# deel1_voeding.net
KiCad netlist of a schematic drawn in Altium Designer
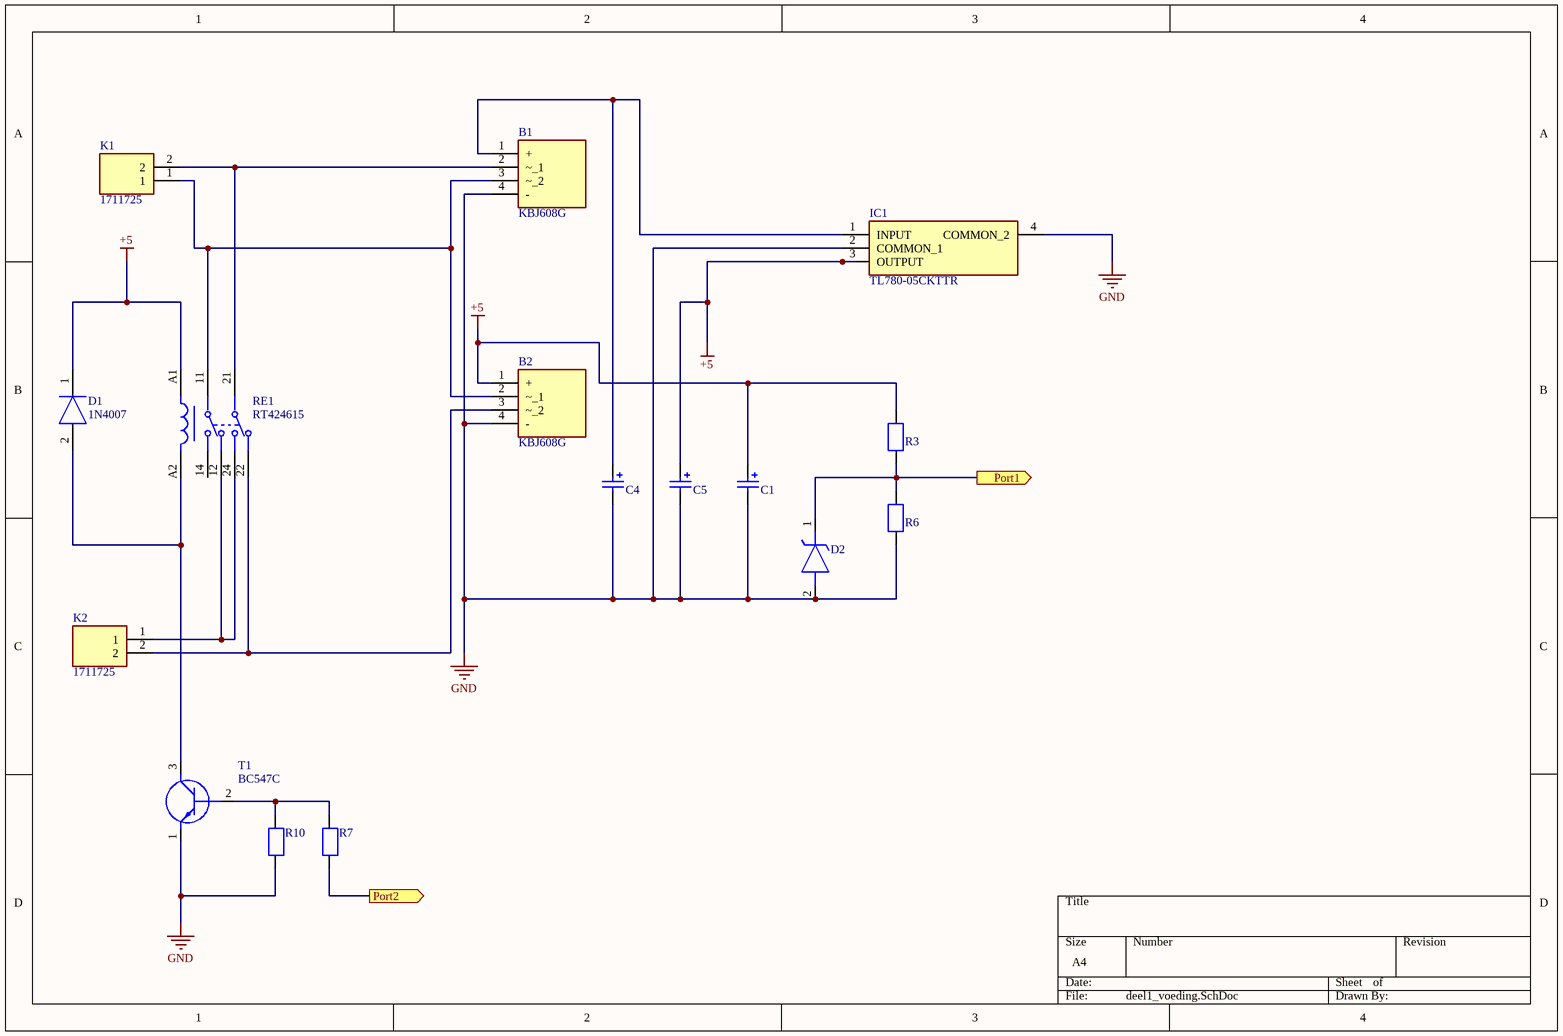
[diagram p0: deel1_voeding.SchDoc]

(export (version "E")
  (design (tool "Eeschema 10.0.6"))
  (components
    (comp (ref "B1")
      (value "KBJ608G")
      (footprint "SamacSys:TO750P480X2500X1900-4P")
      (description "Bridge Rectifier")
      (fields (field (name "MOUSER PART NUMBER") "621-KBJ608G"))
      (libsource (lib "SoldeerboutLib") (part "KBJ608G"))
    )
    (comp (ref "B2")
      (value "KBJ608G")
      (footprint "SamacSys:TO750P480X2500X1900-4P")
      (description "Bridge Rectifier")
      (fields (field (name "MOUSER PART NUMBER") "621-KBJ608G"))
      (libsource (lib "SoldeerboutLib") (part "KBJ608G"))
    )
    (comp (ref "C1")
      (value "4700uF")
      (footprint "WCAP-ATG8_D22H41")
      (description "WCAP-ATG8 Aluminum Electrolytic Capacitor, Radial THT, D22xH41mm, 4700uF, 50V")
      (fields
        (field (name "MANUFACTURER") "Wurth Elektronik")
        (field (name "MANUFACTURER PART NUMBER") "860010683032")
      )
      (libsource (lib "SoldeerboutLib") (part "860010683032"))
    )
    (comp (ref "C4")
      (value "100uF")
      (footprint "WCAP-ATG8_D8H11.5")
      (description "WCAP-ATG8 Aluminum Electrolytic Capacitor, Radial THT, D8xH11.5mm, 100uF, 50V")
      (fields
        (field (name "MANUFACTURER") "Wurth Elektronik")
        (field (name "MANUFACTURER PART NUMBER") "860010674014")
      )
      (libsource (lib "SoldeerboutLib") (part "860010674014"))
    )
    (comp (ref "C5")
      (value "10uF")
      (footprint "WCAP-ATG8_D5H11")
      (description "WCAP-ATG8 Aluminum Electrolytic Capacitor, Radial THT, D5xH11mm, 10uF, 50V")
      (fields
        (field (name "MANUFACTURER") "Wurth Elektronik")
        (field (name "MANUFACTURER PART NUMBER") "860010672009")
      )
      (libsource (lib "SoldeerboutLib") (part "860010672009"))
    )
    (comp (ref "D1")
      (value "1N4007")
      (footprint "SamacSys:DIOM5327X242N")
      (description "Diode")
      (libsource (lib "SoldeerboutLib") (part "1N4007"))
    )
    (comp (ref "D2")
      (value "1N4106")
      (footprint "SamacSys:DIOAD1256W51L444D203")
      (description "Zener Diode")
      (fields (field (name "MOUSER PART NUMBER") "494-1N4106"))
      (libsource (lib "SoldeerboutLib") (part "1N4106"))
    )
    (comp (ref "IC1")
      (value "TL780-05CKTTR")
      (footprint "SamacSys:TL78005CKTTR")
      (description "Integrated Circuit")
      (fields (field (name "MOUSER PART NUMBER") "595-TL780-05CKTTR"))
      (libsource (lib "SoldeerboutLib") (part "TL780-05CKTTR"))
    )
    (comp (ref "K1")
      (value "1711725")
      (footprint "SamacSys:1711725")
      (description "Connector")
      (fields (field (name "MOUSER PART NUMBER") "651-1711725"))
      (libsource (lib "SoldeerboutLib") (part "1711725"))
    )
    (comp (ref "K2")
      (value "1711725")
      (footprint "SamacSys:1711725")
      (description "Connector")
      (fields (field (name "MOUSER PART NUMBER") "651-1711725"))
      (libsource (lib "") (part "1711725_1"))
    )
    (comp (ref "R3")
      (value "CRCW08050000Z0EA")
      (footprint "RESC2013X50X30LL20T20")
      (fields (field (name "MANUFACTURER") "Vishay Dale"))
      (libsource (lib "SoldeerboutLib") (part "resistor"))
    )
    (comp (ref "R6")
      (value "CRCW08050000Z0EA")
      (footprint "RESC2013X50X30LL20T20")
      (fields (field (name "MANUFACTURER") "Vishay Dale"))
      (libsource (lib "SoldeerboutLib") (part "resistor"))
    )
    (comp (ref "R7")
      (value "CRCW08050000Z0EA")
      (footprint "RESC2013X50X30LL20T20")
      (description "10k")
      (fields (field (name "MANUFACTURER") "Vishay Dale"))
      (libsource (lib "SoldeerboutLib") (part "resistor"))
    )
    (comp (ref "R10")
      (value "CRCW08050000Z0EA")
      (footprint "RESC2013X50X30LL20T20")
      (description "4k7")
      (fields (field (name "MANUFACTURER") "Vishay Dale"))
      (libsource (lib "SoldeerboutLib") (part "resistor"))
    )
    (comp (ref "RE1")
      (value "RT424615")
      (footprint "FP-RT424615-MFG")
      (description "RELAY GEN PURPOSE DPDT 8A 115V")
      (libsource (lib "SoldeerboutLib") (part "CMP-03395-000241-1"))
    )
    (comp (ref "T1")
      (value "BC547C")
      (footprint "SamacSys:BC547C")
      (description "Transistor BJT NPN")
      (fields (field (name "MOUSER PART NUMBER") "771-BC547C"))
      (libsource (lib "SoldeerboutLib") (part "BC547C"))
    )
  )
  (nets
    (net (code "1") (name "+5") (class "Default")
      (node (ref "B2") (pin "1") (pinfunction "+_1") (pintype "passive"))
      (node (ref "C1") (pin "1") (pinfunction "P_1") (pintype "passive"))
      (node (ref "C5") (pin "1") (pinfunction "P_1") (pintype "passive"))
      (node (ref "D1") (pin "1") (pinfunction "K_1") (pintype "passive"))
      (node (ref "IC1") (pin "3") (pinfunction "OUTPUT_3") (pintype "passive"))
      (node (ref "R3") (pin "2") (pinfunction "2_2") (pintype "passive"))
      (node (ref "RE1") (pin "A1") (pinfunction "A1_A1") (pintype "passive"))
    )
    (net (code "2") (name "/Port1") (class "Default")
      (node (ref "D2") (pin "1") (pinfunction "K_1") (pintype "passive"))
      (node (ref "R3") (pin "1") (pinfunction "1_1") (pintype "passive"))
      (node (ref "R6") (pin "2") (pinfunction "2_2") (pintype "passive"))
    )
    (net (code "3") (name "/Port2") (class "Default")
      (node (ref "R7") (pin "1") (pinfunction "1_1") (pintype "passive"))
    )
    (net (code "4") (name "GND") (class "Default")
      (node (ref "B1") (pin "4") (pinfunction "-_4") (pintype "passive"))
      (node (ref "B2") (pin "4") (pinfunction "-_4") (pintype "passive"))
      (node (ref "C1") (pin "2") (pinfunction "N_2") (pintype "passive"))
      (node (ref "C4") (pin "2") (pinfunction "N_2") (pintype "passive"))
      (node (ref "C5") (pin "2") (pinfunction "N_2") (pintype "passive"))
      (node (ref "D2") (pin "2") (pinfunction "A_2") (pintype "passive"))
      (node (ref "IC1") (pin "2") (pinfunction "COMMON_1_2") (pintype "passive"))
      (node (ref "IC1") (pin "4") (pinfunction "COMMON_2_4") (pintype "passive"))
      (node (ref "R10") (pin "1") (pinfunction "1_1") (pintype "passive"))
      (node (ref "R6") (pin "1") (pinfunction "1_1") (pintype "passive"))
      (node (ref "T1") (pin "1") (pinfunction "E_1") (pintype "passive"))
    )
    (net (code "5") (name "Net-(B1-+)") (class "Default")
      (node (ref "B1") (pin "1") (pinfunction "+_1") (pintype "passive"))
      (node (ref "C4") (pin "1") (pinfunction "P_1") (pintype "passive"))
      (node (ref "IC1") (pin "1") (pinfunction "INPUT_1") (pintype "passive"))
    )
    (net (code "6") (name "Net-(B1-~_1)") (class "Default")
      (node (ref "B1") (pin "2") (pinfunction "~_1_2") (pintype "passive"))
      (node (ref "K1") (pin "2") (pinfunction "2_2") (pintype "passive"))
      (node (ref "RE1") (pin "21") (pinfunction "21_21") (pintype "passive"))
    )
    (net (code "7") (name "Net-(B1-~_2)") (class "Default")
      (node (ref "B1") (pin "3") (pinfunction "~_2_3") (pintype "passive"))
      (node (ref "B2") (pin "2") (pinfunction "~_1_2") (pintype "passive"))
      (node (ref "K1") (pin "1") (pinfunction "1_1") (pintype "passive"))
      (node (ref "RE1") (pin "11") (pinfunction "11_11") (pintype "passive"))
    )
    (net (code "8") (name "Net-(B2-~_2)") (class "Default")
      (node (ref "B2") (pin "3") (pinfunction "~_2_3") (pintype "passive"))
      (node (ref "K2") (pin "2") (pinfunction "2_2") (pintype "passive"))
      (node (ref "RE1") (pin "22") (pinfunction "22_22") (pintype "passive"))
    )
    (net (code "9") (name "Net-(D1-A)") (class "Default")
      (node (ref "D1") (pin "2") (pinfunction "A_2") (pintype "passive"))
      (node (ref "RE1") (pin "A2") (pinfunction "A2_A2") (pintype "passive"))
      (node (ref "T1") (pin "3") (pinfunction "C_3") (pintype "passive"))
    )
    (net (code "10") (name "Net-(K2-Pad1)") (class "Default")
      (node (ref "K2") (pin "1") (pinfunction "1_1") (pintype "passive"))
      (node (ref "RE1") (pin "12") (pinfunction "12_12") (pintype "passive"))
      (node (ref "RE1") (pin "24") (pinfunction "24_24") (pintype "passive"))
    )
    (net (code "11") (name "Net-(T1-B)") (class "Default")
      (node (ref "R10") (pin "2") (pinfunction "2_2") (pintype "passive"))
      (node (ref "R7") (pin "2") (pinfunction "2_2") (pintype "passive"))
      (node (ref "T1") (pin "2") (pinfunction "B_2") (pintype "passive"))
    )
    (net (code "12") (name "unconnected-(RE1-Pad14)") (class "Default")
      (node (ref "RE1") (pin "14") (pinfunction "14_14") (pintype "passive"))
    )
  )
)
